# LSM6DSV16-_BlueBerry.net
KiCad netlist of a schematic drawn in EasyEDA Pro
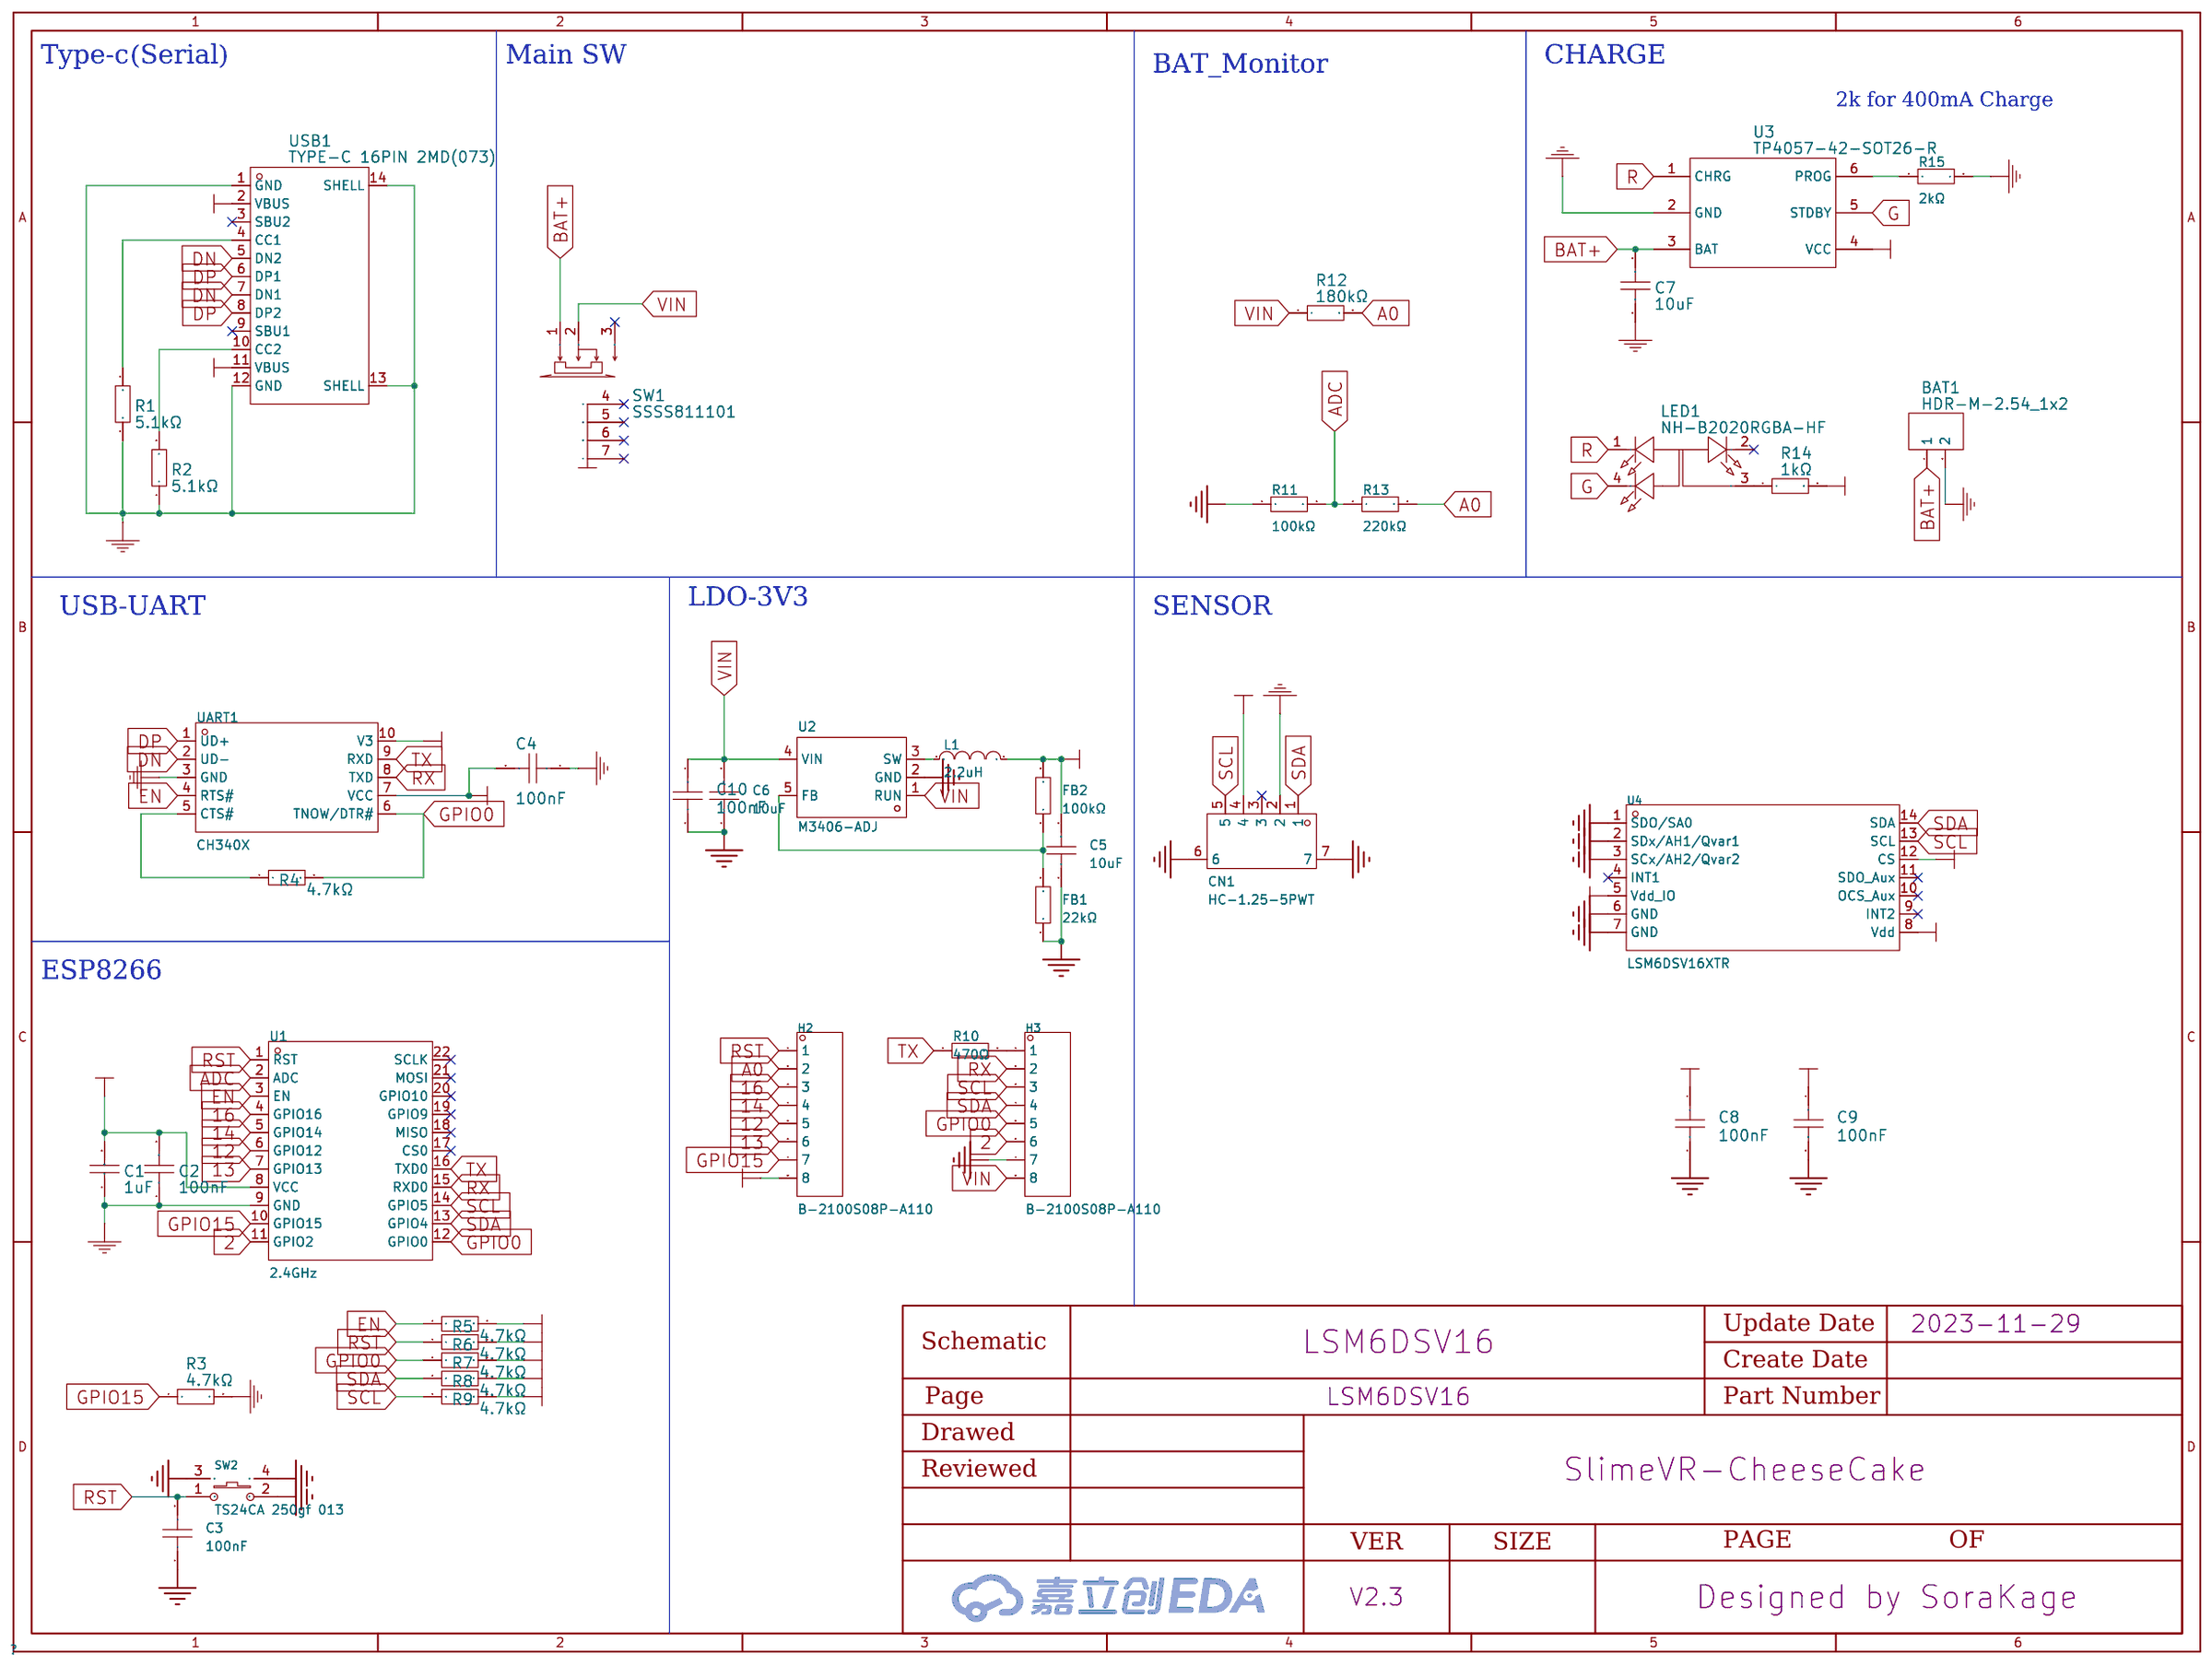
[diagram p0: schematic sheet]

(export (version "E")
  (design (tool "Eeschema 10.0.6"))
  (components
    (comp (ref "BAT1")
      (value "HDR-M-2.54_1x2")
      (footprint "easyedapro:HDR-M-2.54_1X2")
      (libsource (lib "easyedapro") (part "HDR-M-2.54_1x2"))
    )
    (comp (ref "C1")
      (value "1uF")
      (footprint "easyedapro:C0603")
      (fields
        (field (name "Manufacturer Part") "CL10A105KB8NNNC")
        (field (name "Manufacturer") "SAMSUNG(三星)")
      )
      (libsource (lib "easyedapro") (part "1uF"))
    )
    (comp (ref "C2")
      (value "100nF")
      (footprint "easyedapro:C0603")
      (fields
        (field (name "Manufacturer Part") "CC0603KRX7R9BB104")
        (field (name "Manufacturer") "YAGEO(国巨)")
      )
      (libsource (lib "easyedapro") (part "100nF"))
    )
    (comp (ref "C3")
      (value "100nF")
      (footprint "easyedapro:C0603")
      (description "容值:100nF;精度:±10%;额定电压:50V;材质(温度系数):X7R;")
      (fields
        (field (name "Manufacturer Part") "CC0603KRX7R9BB104")
        (field (name "Manufacturer") "YAGEO(国巨)")
      )
      (libsource (lib "easyedapro") (part "CC0603KRX7R9BB104"))
    )
    (comp (ref "C4")
      (value "100nF")
      (footprint "easyedapro:C0603")
      (fields
        (field (name "Manufacturer Part") "CC0603KRX7R9BB104")
        (field (name "Manufacturer") "YAGEO(国巨)")
      )
      (libsource (lib "easyedapro") (part "100nF"))
    )
    (comp (ref "C5")
      (value "10uF")
      (footprint "easyedapro:C0603")
      (description "容值:10uF;精度:±10%;额定电压:10V;材质(温度系数):X5R;")
      (fields
        (field (name "Manufacturer Part") "CL10A106KP8NNNC")
        (field (name "Manufacturer") "SAMSUNG(三星)")
      )
      (libsource (lib "easyedapro") (part "CL10A106KP8NNNC"))
    )
    (comp (ref "C6")
      (value "10uF")
      (footprint "easyedapro:C0603")
      (description "容值:10uF;精度:±10%;额定电压:10V;材质(温度系数):X5R;")
      (fields
        (field (name "Manufacturer Part") "CL10A106KP8NNNC")
        (field (name "Manufacturer") "SAMSUNG(三星)")
      )
      (libsource (lib "easyedapro") (part "CL10A106KP8NNNC"))
    )
    (comp (ref "C7")
      (value "10uF")
      (footprint "easyedapro:C0603")
      (fields
        (field (name "Manufacturer Part") "CL10A106KP8NNNC")
        (field (name "Manufacturer") "SAMSUNG(三星)")
      )
      (libsource (lib "easyedapro") (part "10uF"))
    )
    (comp (ref "C8")
      (value "100nF")
      (footprint "easyedapro:C0603")
      (fields
        (field (name "Manufacturer Part") "CC0603KRX7R9BB104")
        (field (name "Manufacturer") "YAGEO(国巨)")
      )
      (libsource (lib "easyedapro") (part "100nF"))
    )
    (comp (ref "C9")
      (value "100nF")
      (footprint "easyedapro:C0603")
      (fields
        (field (name "Manufacturer Part") "CC0603KRX7R9BB104")
        (field (name "Manufacturer") "YAGEO(国巨)")
      )
      (libsource (lib "easyedapro") (part "100nF"))
    )
    (comp (ref "C10")
      (value "100nF")
      (footprint "easyedapro:C0603")
      (fields
        (field (name "Manufacturer Part") "CC0603KRX7R9BB104")
        (field (name "Manufacturer") "YAGEO(国巨)")
      )
      (libsource (lib "easyedapro") (part "100nF"))
    )
    (comp (ref "CN1")
      (value "HC-1.25-5PWT")
      (footprint "easyedapro:CONN-SMD_5P-P1.25_HCTL_HC-1.25-5PWT")
      (description "参考系列:-;间距:1.25mm;插针结构:1x5P;排数:1;每排PIN数:5;行距:-;公母:公型插针;安装方式:卧贴;额定电流:1A;工作温度范围:-25°C~+85°C;")
      (fields (field (name "Manufacturer") "HCTL(华灿天禄)"))
      (libsource (lib "easyedapro") (part "HC-1.25-5PWT"))
    )
    (comp (ref "FB1")
      (value "22kΩ")
      (footprint "easyedapro:R0402")
      (description "电阻类型:厚膜电阻;阻值:22kΩ;精度:±1%;功率:62.5mW;")
      (fields
        (field (name "Manufacturer Part") "0402WGF2202TCE")
        (field (name "Manufacturer") "UNI-ROYAL(厚声)")
      )
      (libsource (lib "easyedapro") (part "0402WGF2202TCE"))
    )
    (comp (ref "FB2")
      (value "100kΩ")
      (footprint "easyedapro:R0402")
      (description "电阻类型:厚膜电阻;阻值:100kΩ;精度:±1%;功率:62.5mW;")
      (fields
        (field (name "Manufacturer Part") "0402WGF1003TCE")
        (field (name "Manufacturer") "UNI-ROYAL(厚声)")
      )
      (libsource (lib "easyedapro") (part "0402WGF1003TCE"))
    )
    (comp (ref "H2")
      (value "B-2100S08P-A110")
      (footprint "easyedapro:HDR-TH_8P-P2.54-V-M")
      (fields (field (name "Manufacturer") "Ckmtw(灿科盟)"))
      (libsource (lib "easyedapro") (part "Header-Male-2.54_1x8"))
    )
    (comp (ref "H3")
      (value "B-2100S08P-A110")
      (footprint "easyedapro:HDR-TH_8P-P2.54-V-M")
      (fields (field (name "Manufacturer") "Ckmtw(灿科盟)"))
      (libsource (lib "easyedapro") (part "Header-Male-2.54_1x8"))
    )
    (comp (ref "L1")
      (value "2.2uH")
      (footprint "easyedapro:IND-SMD_L2.5-W2.0_YXMBL252010P")
      (description "类型:一体成型电感;电感值:2.2uH;精度:±20%;额定电流:2.1A;饱和电流(Isat):3A;")
      (fields (field (name "Manufacturer Part") "APH252010T2R2M") (field (name "Manufacturer") "APV(爱普微)"))
      (libsource (lib "easyedapro") (part "APH252010T2R2M"))
    )
    (comp (ref "LED1")
      (value "NH-B2020RGBA-HF")
      (footprint "easyedapro:LED-ARRAY-SMD_4P-L2.1-W2.1-TL_NH-B2020RGBA")
      (fields (field (name "Manufacturer") "国星光电"))
      (libsource (lib "easyedapro") (part "NH-B2020RGBA-HF"))
    )
    (comp (ref "R1")
      (value "5.1kΩ")
      (footprint "easyedapro:R0603")
      (fields
        (field (name "Manufacturer Part") "0603WAF5101T5E")
        (field (name "Manufacturer") "UNI-ROYAL(厚声)")
      )
      (libsource (lib "easyedapro") (part "5.1kΩ"))
    )
    (comp (ref "R2")
      (value "5.1kΩ")
      (footprint "easyedapro:R0603")
      (fields
        (field (name "Manufacturer Part") "0603WAF5101T5E")
        (field (name "Manufacturer") "UNI-ROYAL(厚声)")
      )
      (libsource (lib "easyedapro") (part "5.1kΩ"))
    )
    (comp (ref "R3")
      (value "4.7kΩ")
      (footprint "easyedapro:R0603")
      (fields
        (field (name "Manufacturer Part") "0603WAF4701T5E")
        (field (name "Manufacturer") "UNI-ROYAL(厚声)")
      )
      (libsource (lib "easyedapro") (part "4.7kΩ"))
    )
    (comp (ref "R4")
      (value "4.7kΩ")
      (footprint "easyedapro:R0603")
      (fields
        (field (name "Manufacturer Part") "0603WAF4701T5E")
        (field (name "Manufacturer") "UNI-ROYAL(厚声)")
      )
      (libsource (lib "easyedapro") (part "4.7kΩ"))
    )
    (comp (ref "R5")
      (value "4.7kΩ")
      (footprint "easyedapro:R0603")
      (fields
        (field (name "Manufacturer Part") "0603WAF4701T5E")
        (field (name "Manufacturer") "UNI-ROYAL(厚声)")
      )
      (libsource (lib "easyedapro") (part "4.7kΩ"))
    )
    (comp (ref "R6")
      (value "4.7kΩ")
      (footprint "easyedapro:R0603")
      (fields
        (field (name "Manufacturer Part") "0603WAF4701T5E")
        (field (name "Manufacturer") "UNI-ROYAL(厚声)")
      )
      (libsource (lib "easyedapro") (part "4.7kΩ"))
    )
    (comp (ref "R7")
      (value "4.7kΩ")
      (footprint "easyedapro:R0603")
      (fields
        (field (name "Manufacturer Part") "0603WAF4701T5E")
        (field (name "Manufacturer") "UNI-ROYAL(厚声)")
      )
      (libsource (lib "easyedapro") (part "4.7kΩ"))
    )
    (comp (ref "R8")
      (value "4.7kΩ")
      (footprint "easyedapro:R0603")
      (fields
        (field (name "Manufacturer Part") "0603WAF4701T5E")
        (field (name "Manufacturer") "UNI-ROYAL(厚声)")
      )
      (libsource (lib "easyedapro") (part "4.7kΩ"))
    )
    (comp (ref "R9")
      (value "4.7kΩ")
      (footprint "easyedapro:R0603")
      (fields
        (field (name "Manufacturer Part") "0603WAF4701T5E")
        (field (name "Manufacturer") "UNI-ROYAL(厚声)")
      )
      (libsource (lib "easyedapro") (part "4.7kΩ"))
    )
    (comp (ref "R10")
      (value "470Ω")
      (footprint "easyedapro:R0603")
      (description "电阻类型:厚膜电阻;阻值:470Ω;精度:±1%;功率:100mW;")
      (fields
        (field (name "Manufacturer Part") "0603WAF4700T5E")
        (field (name "Manufacturer") "UNI-ROYAL(厚声)")
      )
      (libsource (lib "easyedapro") (part "0603WAF4700T5E"))
    )
    (comp (ref "R11")
      (value "100kΩ")
      (footprint "easyedapro:R0603")
      (description "电阻类型:厚膜电阻;阻值:100kΩ;精度:±1%;功率:100mW;")
      (fields
        (field (name "Manufacturer Part") "0603WAF1003T5E")
        (field (name "Manufacturer") "UNI-ROYAL(厚声)")
      )
      (libsource (lib "easyedapro") (part "0603WAF1003T5E"))
    )
    (comp (ref "R12")
      (value "180kΩ")
      (footprint "easyedapro:R0603")
      (fields
        (field (name "Manufacturer Part") "0603WAF1803T5E")
        (field (name "Manufacturer") "UNI-ROYAL(厚声)")
      )
      (libsource (lib "easyedapro") (part "180kΩ"))
    )
    (comp (ref "R13")
      (value "220kΩ")
      (footprint "easyedapro:R0603")
      (description "电阻类型:厚膜电阻;阻值:220kΩ;精度:±1%;功率:100mW;")
      (fields
        (field (name "Manufacturer Part") "0603WAF2203T5E")
        (field (name "Manufacturer") "UNI-ROYAL(厚声)")
      )
      (libsource (lib "easyedapro") (part "0603WAF2203T5E"))
    )
    (comp (ref "R14")
      (value "1kΩ")
      (footprint "easyedapro:R0603")
      (fields
        (field (name "Manufacturer Part") "0603WAF1001T5E")
        (field (name "Manufacturer") "UNI-ROYAL(厚声)")
      )
      (libsource (lib "easyedapro") (part "1kΩ"))
    )
    (comp (ref "R15")
      (value "2kΩ")
      (footprint "easyedapro:R0603")
      (description "电阻类型:厚膜电阻;阻值:2kΩ;精度:±1%;功率:100mW;")
      (fields
        (field (name "Manufacturer Part") "0603WAF2001T5E")
        (field (name "Manufacturer") "UNI-ROYAL(厚声)")
      )
      (libsource (lib "easyedapro") (part "0603WAF2001T5E"))
    )
    (comp (ref "SW1")
      (value "SSSS811101")
      (footprint "easyedapro:SW-SMD_SSSS811101")
      (fields (field (name "Manufacturer") "ALPSALPINE(阿尔卑斯阿尔派)"))
      (libsource (lib "easyedapro") (part "SSSS811101"))
    )
    (comp (ref "SW2")
      (value "TS24CA 250gf 013")
      (footprint "easyedapro:SW-SMD_L4.7-W3.5-P3.35-EH")
      (fields (field (name "Manufacturer") "SHOU HAN(首韩)"))
      (libsource (lib "easyedapro") (part "TS24CA 250GF 013"))
    )
    (comp (ref "U1")
      (value "2.4GHz")
      (footprint "easyedapro:WIFIM-SMD_ESP-12F-ESP8266MOD")
      (description "频率:2.4GHz;发射功率:16dBm;核心处理器:ESP8266;天线形式:PCB 板载天线;接收灵敏度:-90dBm;")
      (fields
        (field (name "Manufacturer Part") "ESP-12F(ESP8266MOD)")
        (field (name "Manufacturer") "Ai-Thinker(安信可)")
      )
      (libsource (lib "easyedapro") (part "ESP-12F(ESP8266MOD)"))
    )
    (comp (ref "U2")
      (value "M3406-ADJ")
      (footprint "easyedapro:SOT-23-5_L3.0-W1.7-P0.95-LS2.8-BR")
      (description "功能类型:降压型;同步整流:-;输出通道数:-;拓扑结构:-;输入电压:-;输出电流(最大值):-;开关频率:-;")
      (fields (field (name "Manufacturer") "西安航天民芯"))
      (libsource (lib "easyedapro") (part "M3406"))
    )
    (comp (ref "U3")
      (value "TP4057-42-SOT26-R")
      (footprint "easyedapro:SOT-23-6_L2.9-W1.6-P0.95-LS2.8-BL")
      (fields (field (name "Manufacturer") "TOPPOWER(南京拓微)"))
      (libsource (lib "easyedapro") (part "TP4057"))
    )
    (comp (ref "U4")
      (value "LSM6DSV16XTR")
      (footprint "easyedapro:LGA-14_L3.0-W2.5-P0.50-BR")
      (description "传感器类型:加速度计陀螺仪;")
      (fields (field (name "Manufacturer") "ST(意法半导体)"))
      (libsource (lib "easyedapro") (part "LSM6DSV16XTR"))
    )
    (comp (ref "UART1")
      (value "CH340X")
      (footprint "easyedapro:MSOP-10_L3.0-W3.0-P0.50-LS5.0-BL")
      (fields (field (name "Manufacturer") "WCH(南京沁恒)"))
      (libsource (lib "easyedapro") (part "CH340X"))
    )
    (comp (ref "USB1")
      (value "TYPE-C 16PIN 2MD(073)")
      (footprint "easyedapro:USB-C-SMD_TYPE-C-6PIN-2MD-073")
      (fields (field (name "Manufacturer") "SHOU HAN(首韩)"))
      (libsource (lib "easyedapro") (part "TYPE-C 16PIN 2MD(073)"))
    )
  )
  (nets
    (net (code "1") (name "+5V") (class "Default")
      (node (ref "R14") (pin "2") (pinfunction "2_2") (pintype "input"))
      (node (ref "U3") (pin "4") (pinfunction "VCC_4") (pintype "unspecified"))
      (node (ref "USB1") (pin "11") (pinfunction "VBUS_11") (pintype "input"))
      (node (ref "USB1") (pin "2") (pinfunction "VBUS_2") (pintype "input"))
    )
    (net (code "2") (name "2") (class "Default")
      (node (ref "H3") (pin "6") (pinfunction "6_6") (pintype "input"))
      (node (ref "U1") (pin "11") (pinfunction "GPIO2_11") (pintype "input"))
    )
    (net (code "3") (name "3V3") (class "Default")
      (node (ref "C1") (pin "2") (pinfunction "2_2") (pintype "input"))
      (node (ref "C2") (pin "2") (pinfunction "2_2") (pintype "input"))
      (node (ref "C4") (pin "2") (pinfunction "2_2") (pintype "input"))
      (node (ref "C5") (pin "2") (pinfunction "2_2") (pintype "unspecified"))
      (node (ref "C8") (pin "1") (pinfunction "1_1") (pintype "input"))
      (node (ref "C9") (pin "1") (pinfunction "1_1") (pintype "input"))
      (node (ref "CN1") (pin "4") (pinfunction "4_4") (pintype "unspecified"))
      (node (ref "FB2") (pin "2") (pinfunction "2_2") (pintype "input"))
      (node (ref "H2") (pin "8") (pinfunction "8_8") (pintype "input"))
      (node (ref "L1") (pin "2") (pinfunction "2_2") (pintype "unspecified"))
      (node (ref "R5") (pin "2") (pinfunction "2_2") (pintype "input"))
      (node (ref "R6") (pin "2") (pinfunction "2_2") (pintype "input"))
      (node (ref "R7") (pin "2") (pinfunction "2_2") (pintype "input"))
      (node (ref "R8") (pin "2") (pinfunction "2_2") (pintype "input"))
      (node (ref "R9") (pin "2") (pinfunction "2_2") (pintype "input"))
      (node (ref "U1") (pin "8") (pinfunction "VCC_8") (pintype "input"))
      (node (ref "U4") (pin "12") (pinfunction "CS_12") (pintype "input"))
      (node (ref "U4") (pin "5") (pinfunction "Vdd_IO_5") (pintype "input"))
      (node (ref "U4") (pin "8") (pinfunction "Vdd_8") (pintype "input"))
      (node (ref "UART1") (pin "10") (pinfunction "V3_10") (pintype "unspecified"))
      (node (ref "UART1") (pin "7") (pinfunction "VCC_7") (pintype "unspecified"))
    )
    (net (code "4") (name "12") (class "Default")
      (node (ref "H2") (pin "5") (pinfunction "5_5") (pintype "input"))
      (node (ref "U1") (pin "6") (pinfunction "GPIO12_6") (pintype "input"))
    )
    (net (code "5") (name "13") (class "Default")
      (node (ref "H2") (pin "6") (pinfunction "6_6") (pintype "input"))
      (node (ref "U1") (pin "7") (pinfunction "GPIO13_7") (pintype "input"))
    )
    (net (code "6") (name "14") (class "Default")
      (node (ref "H2") (pin "4") (pinfunction "4_4") (pintype "input"))
      (node (ref "U1") (pin "5") (pinfunction "GPIO14_5") (pintype "input"))
    )
    (net (code "7") (name "16") (class "Default")
      (node (ref "H2") (pin "3") (pinfunction "3_3") (pintype "input"))
      (node (ref "U1") (pin "4") (pinfunction "GPIO16_4") (pintype "input"))
    )
    (net (code "8") (name "A0") (class "Default")
      (node (ref "H2") (pin "2") (pinfunction "2_2") (pintype "input"))
      (node (ref "R12") (pin "2") (pinfunction "2_2") (pintype "input"))
      (node (ref "R13") (pin "2") (pinfunction "2_2") (pintype "input"))
    )
    (net (code "9") (name "ADC") (class "Default")
      (node (ref "R11") (pin "2") (pinfunction "2_2") (pintype "input"))
      (node (ref "R13") (pin "1") (pinfunction "1_1") (pintype "input"))
      (node (ref "U1") (pin "2") (pinfunction "ADC_2") (pintype "input"))
    )
    (net (code "10") (name "BAT+") (class "Default")
      (node (ref "BAT1") (pin "1") (pinfunction "1_1") (pintype "input"))
      (node (ref "C7") (pin "2") (pinfunction "2_2") (pintype "input"))
      (node (ref "SW1") (pin "1") (pinfunction "1_1") (pintype "input"))
      (node (ref "U3") (pin "3") (pinfunction "BAT_3") (pintype "unspecified"))
    )
    (net (code "11") (name "DN") (class "Default")
      (node (ref "UART1") (pin "2") (pinfunction "UD-_2") (pintype "unspecified"))
      (node (ref "USB1") (pin "5") (pinfunction "DN2_5") (pintype "input"))
      (node (ref "USB1") (pin "7") (pinfunction "DN1_7") (pintype "input"))
    )
    (net (code "12") (name "DP") (class "Default")
      (node (ref "UART1") (pin "1") (pinfunction "UD+_1") (pintype "unspecified"))
      (node (ref "USB1") (pin "6") (pinfunction "DP1_6") (pintype "input"))
      (node (ref "USB1") (pin "8") (pinfunction "DP2_8") (pintype "input"))
    )
    (net (code "13") (name "EN") (class "Default")
      (node (ref "R5") (pin "1") (pinfunction "1_1") (pintype "input"))
      (node (ref "U1") (pin "3") (pinfunction "EN_3") (pintype "input"))
      (node (ref "UART1") (pin "4") (pinfunction "RTS#_4") (pintype "unspecified"))
    )
    (net (code "14") (name "G") (class "Default")
      (node (ref "LED1") (pin "4") (pinfunction "-_4") (pintype "input"))
      (node (ref "U3") (pin "5") (pinfunction "STDBY_5") (pintype "unspecified"))
    )
    (net (code "15") (name "GND") (class "Default")
      (node (ref "BAT1") (pin "2") (pinfunction "2_2") (pintype "input"))
      (node (ref "C1") (pin "1") (pinfunction "1_1") (pintype "input"))
      (node (ref "C10") (pin "2") (pinfunction "2_2") (pintype "input"))
      (node (ref "C2") (pin "1") (pinfunction "1_1") (pintype "input"))
      (node (ref "C3") (pin "1") (pinfunction "1_1") (pintype "unspecified"))
      (node (ref "C4") (pin "1") (pinfunction "1_1") (pintype "input"))
      (node (ref "C5") (pin "1") (pinfunction "1_1") (pintype "unspecified"))
      (node (ref "C6") (pin "1") (pinfunction "1_1") (pintype "unspecified"))
      (node (ref "C7") (pin "1") (pinfunction "1_1") (pintype "input"))
      (node (ref "C8") (pin "2") (pinfunction "2_2") (pintype "input"))
      (node (ref "C9") (pin "2") (pinfunction "2_2") (pintype "input"))
      (node (ref "CN1") (pin "2") (pinfunction "2_2") (pintype "unspecified"))
      (node (ref "CN1") (pin "6") (pinfunction "6_6") (pintype "unspecified"))
      (node (ref "CN1") (pin "7") (pinfunction "7_7") (pintype "unspecified"))
      (node (ref "FB1") (pin "1") (pinfunction "1_1") (pintype "input"))
      (node (ref "H3") (pin "7") (pinfunction "7_7") (pintype "input"))
      (node (ref "R1") (pin "1") (pinfunction "1_1") (pintype "input"))
      (node (ref "R11") (pin "1") (pinfunction "1_1") (pintype "input"))
      (node (ref "R15") (pin "2") (pinfunction "2_2") (pintype "input"))
      (node (ref "R2") (pin "1") (pinfunction "1_1") (pintype "input"))
      (node (ref "R3") (pin "2") (pinfunction "2_2") (pintype "input"))
      (node (ref "SW2") (pin "2") (pinfunction "2_2") (pintype "input"))
      (node (ref "SW2") (pin "3") (pinfunction "3_3") (pintype "input"))
      (node (ref "SW2") (pin "4") (pinfunction "4_4") (pintype "input"))
      (node (ref "U1") (pin "9") (pinfunction "GND_9") (pintype "input"))
      (node (ref "U2") (pin "2") (pinfunction "GND_2") (pintype "input"))
      (node (ref "U3") (pin "2") (pinfunction "GND_2") (pintype "unspecified"))
      (node (ref "U4") (pin "1") (pinfunction "SDO/SA0_1") (pintype "input"))
      (node (ref "U4") (pin "2") (pinfunction "SDx/AH1/Qvar1_2") (pintype "input"))
      (node (ref "U4") (pin "3") (pinfunction "SCx/AH2/Qvar2_3") (pintype "input"))
      (node (ref "U4") (pin "6") (pinfunction "GND_6") (pintype "input"))
      (node (ref "U4") (pin "7") (pinfunction "GND_7") (pintype "input"))
      (node (ref "UART1") (pin "3") (pinfunction "GND_3") (pintype "unspecified"))
      (node (ref "USB1") (pin "1") (pinfunction "GND_1") (pintype "input"))
      (node (ref "USB1") (pin "12") (pinfunction "GND_12") (pintype "input"))
      (node (ref "USB1") (pin "13") (pinfunction "SHELL_13") (pintype "input"))
      (node (ref "USB1") (pin "14") (pinfunction "SHELL_14") (pintype "input"))
    )
    (net (code "16") (name "GPIO0") (class "Default")
      (node (ref "H3") (pin "5") (pinfunction "5_5") (pintype "input"))
      (node (ref "R4") (pin "2") (pinfunction "2_2") (pintype "input"))
      (node (ref "R7") (pin "1") (pinfunction "1_1") (pintype "input"))
      (node (ref "U1") (pin "12") (pinfunction "GPIO0_12") (pintype "input"))
      (node (ref "UART1") (pin "6") (pinfunction "TNOW/DTR#_6") (pintype "unspecified"))
    )
    (net (code "17") (name "GPIO15") (class "Default")
      (node (ref "H2") (pin "7") (pinfunction "7_7") (pintype "input"))
      (node (ref "R3") (pin "1") (pinfunction "1_1") (pintype "input"))
      (node (ref "U1") (pin "10") (pinfunction "GPIO15_10") (pintype "input"))
    )
    (net (code "18") (name "Net-(H3-Pad1)") (class "Default")
      (node (ref "H3") (pin "1") (pinfunction "1_1") (pintype "input"))
      (node (ref "R10") (pin "2") (pinfunction "2_2") (pintype "input"))
    )
    (net (code "19") (name "Net-(LED1-+)") (class "Default")
      (node (ref "LED1") (pin "3") (pinfunction "+_3") (pintype "input"))
      (node (ref "R14") (pin "1") (pinfunction "1_1") (pintype "input"))
    )
    (net (code "20") (name "Net-(U2-FB)") (class "Default")
      (node (ref "FB1") (pin "2") (pinfunction "2_2") (pintype "input"))
      (node (ref "FB2") (pin "1") (pinfunction "1_1") (pintype "input"))
      (node (ref "U2") (pin "5") (pinfunction "FB_5") (pintype "input"))
    )
    (net (code "21") (name "Net-(U2-SW)") (class "Default")
      (node (ref "L1") (pin "1") (pinfunction "1_1") (pintype "unspecified"))
      (node (ref "U2") (pin "3") (pinfunction "SW_3") (pintype "input"))
    )
    (net (code "22") (name "Net-(U3-PROG)") (class "Default")
      (node (ref "R15") (pin "1") (pinfunction "1_1") (pintype "input"))
      (node (ref "U3") (pin "6") (pinfunction "PROG_6") (pintype "unspecified"))
    )
    (net (code "23") (name "Net-(UART1-CTS#)") (class "Default")
      (node (ref "R4") (pin "1") (pinfunction "1_1") (pintype "input"))
      (node (ref "UART1") (pin "5") (pinfunction "CTS#_5") (pintype "unspecified"))
    )
    (net (code "24") (name "Net-(USB1-CC1)") (class "Default")
      (node (ref "R1") (pin "2") (pinfunction "2_2") (pintype "input"))
      (node (ref "USB1") (pin "4") (pinfunction "CC1_4") (pintype "input"))
    )
    (net (code "25") (name "Net-(USB1-CC2)") (class "Default")
      (node (ref "R2") (pin "2") (pinfunction "2_2") (pintype "input"))
      (node (ref "USB1") (pin "10") (pinfunction "CC2_10") (pintype "input"))
    )
    (net (code "26") (name "R") (class "Default")
      (node (ref "LED1") (pin "1") (pinfunction "-_1") (pintype "input"))
      (node (ref "U3") (pin "1") (pinfunction "CHRG_1") (pintype "unspecified"))
    )
    (net (code "27") (name "RST") (class "Default")
      (node (ref "C3") (pin "2") (pinfunction "2_2") (pintype "unspecified"))
      (node (ref "H2") (pin "1") (pinfunction "1_1") (pintype "input"))
      (node (ref "R6") (pin "1") (pinfunction "1_1") (pintype "input"))
      (node (ref "SW2") (pin "1") (pinfunction "1_1") (pintype "input"))
      (node (ref "U1") (pin "1") (pinfunction "RST_1") (pintype "input"))
    )
    (net (code "28") (name "RX") (class "Default")
      (node (ref "H3") (pin "2") (pinfunction "2_2") (pintype "input"))
      (node (ref "U1") (pin "15") (pinfunction "RXD0_15") (pintype "input"))
      (node (ref "UART1") (pin "8") (pinfunction "TXD_8") (pintype "unspecified"))
    )
    (net (code "29") (name "SCL") (class "Default")
      (node (ref "CN1") (pin "5") (pinfunction "5_5") (pintype "unspecified"))
      (node (ref "H3") (pin "3") (pinfunction "3_3") (pintype "input"))
      (node (ref "R9") (pin "1") (pinfunction "1_1") (pintype "input"))
      (node (ref "U1") (pin "14") (pinfunction "GPIO5_14") (pintype "input"))
      (node (ref "U4") (pin "13") (pinfunction "SCL_13") (pintype "input"))
    )
    (net (code "30") (name "SDA") (class "Default")
      (node (ref "CN1") (pin "1") (pinfunction "1_1") (pintype "unspecified"))
      (node (ref "H3") (pin "4") (pinfunction "4_4") (pintype "input"))
      (node (ref "R8") (pin "1") (pinfunction "1_1") (pintype "input"))
      (node (ref "U1") (pin "13") (pinfunction "GPIO4_13") (pintype "input"))
      (node (ref "U4") (pin "14") (pinfunction "SDA_14") (pintype "input"))
    )
    (net (code "31") (name "TX") (class "Default")
      (node (ref "R10") (pin "1") (pinfunction "1_1") (pintype "input"))
      (node (ref "U1") (pin "16") (pinfunction "TXD0_16") (pintype "input"))
      (node (ref "UART1") (pin "9") (pinfunction "RXD_9") (pintype "unspecified"))
    )
    (net (code "32") (name "VIN") (class "Default")
      (node (ref "C10") (pin "1") (pinfunction "1_1") (pintype "input"))
      (node (ref "C6") (pin "2") (pinfunction "2_2") (pintype "unspecified"))
      (node (ref "H3") (pin "8") (pinfunction "8_8") (pintype "input"))
      (node (ref "R12") (pin "1") (pinfunction "1_1") (pintype "input"))
      (node (ref "SW1") (pin "2") (pinfunction "2_2") (pintype "input"))
      (node (ref "U2") (pin "1") (pinfunction "RUN_1") (pintype "input"))
      (node (ref "U2") (pin "4") (pinfunction "VIN_4") (pintype "input"))
    )
    (net (code "33") (name "unconnected-(CN1-Pad3)") (class "Default")
      (node (ref "CN1") (pin "3") (pinfunction "3_3") (pintype "unspecified+no_connect"))
    )
    (net (code "34") (name "unconnected-(LED1---Pad2)") (class "Default")
      (node (ref "LED1") (pin "2") (pinfunction "-_2") (pintype "input+no_connect"))
    )
    (net (code "35") (name "unconnected-(SW1-Pad3)") (class "Default")
      (node (ref "SW1") (pin "3") (pinfunction "3_3") (pintype "input+no_connect"))
    )
    (net (code "36") (name "unconnected-(SW1-Pad4)") (class "Default")
      (node (ref "SW1") (pin "4") (pinfunction "4_4") (pintype "input+no_connect"))
    )
    (net (code "37") (name "unconnected-(SW1-Pad5)") (class "Default")
      (node (ref "SW1") (pin "5") (pinfunction "5_5") (pintype "input+no_connect"))
    )
    (net (code "38") (name "unconnected-(SW1-Pad6)") (class "Default")
      (node (ref "SW1") (pin "6") (pinfunction "6_6") (pintype "input+no_connect"))
    )
    (net (code "39") (name "unconnected-(SW1-Pad7)") (class "Default")
      (node (ref "SW1") (pin "7") (pinfunction "7_7") (pintype "input+no_connect"))
    )
    (net (code "40") (name "unconnected-(U1-CS0-Pad17)") (class "Default")
      (node (ref "U1") (pin "17") (pinfunction "CS0_17") (pintype "input+no_connect"))
    )
    (net (code "41") (name "unconnected-(U1-GPIO9-Pad19)") (class "Default")
      (node (ref "U1") (pin "19") (pinfunction "GPIO9_19") (pintype "input+no_connect"))
    )
    (net (code "42") (name "unconnected-(U1-GPIO10-Pad20)") (class "Default")
      (node (ref "U1") (pin "20") (pinfunction "GPIO10_20") (pintype "input+no_connect"))
    )
    (net (code "43") (name "unconnected-(U1-MISO-Pad18)") (class "Default")
      (node (ref "U1") (pin "18") (pinfunction "MISO_18") (pintype "input+no_connect"))
    )
    (net (code "44") (name "unconnected-(U1-MOSI-Pad21)") (class "Default")
      (node (ref "U1") (pin "21") (pinfunction "MOSI_21") (pintype "input+no_connect"))
    )
    (net (code "45") (name "unconnected-(U1-SCLK-Pad22)") (class "Default")
      (node (ref "U1") (pin "22") (pinfunction "SCLK_22") (pintype "input+no_connect"))
    )
    (net (code "46") (name "unconnected-(U4-INT1-Pad4)") (class "Default")
      (node (ref "U4") (pin "4") (pinfunction "INT1_4") (pintype "input+no_connect"))
    )
    (net (code "47") (name "unconnected-(U4-INT2-Pad9)") (class "Default")
      (node (ref "U4") (pin "9") (pinfunction "INT2_9") (pintype "input+no_connect"))
    )
    (net (code "48") (name "unconnected-(U4-OCS_Aux-Pad10)") (class "Default")
      (node (ref "U4") (pin "10") (pinfunction "OCS_Aux_10") (pintype "input+no_connect"))
    )
    (net (code "49") (name "unconnected-(U4-SDO_Aux-Pad11)") (class "Default")
      (node (ref "U4") (pin "11") (pinfunction "SDO_Aux_11") (pintype "input+no_connect"))
    )
    (net (code "50") (name "unconnected-(USB1-SBU1-Pad9)") (class "Default")
      (node (ref "USB1") (pin "9") (pinfunction "SBU1_9") (pintype "input+no_connect"))
    )
    (net (code "51") (name "unconnected-(USB1-SBU2-Pad3)") (class "Default")
      (node (ref "USB1") (pin "3") (pinfunction "SBU2_3") (pintype "input+no_connect"))
    )
  )
)
